# sdc_Sch.net
KiCad netlist of a schematic drawn in Altium Designer
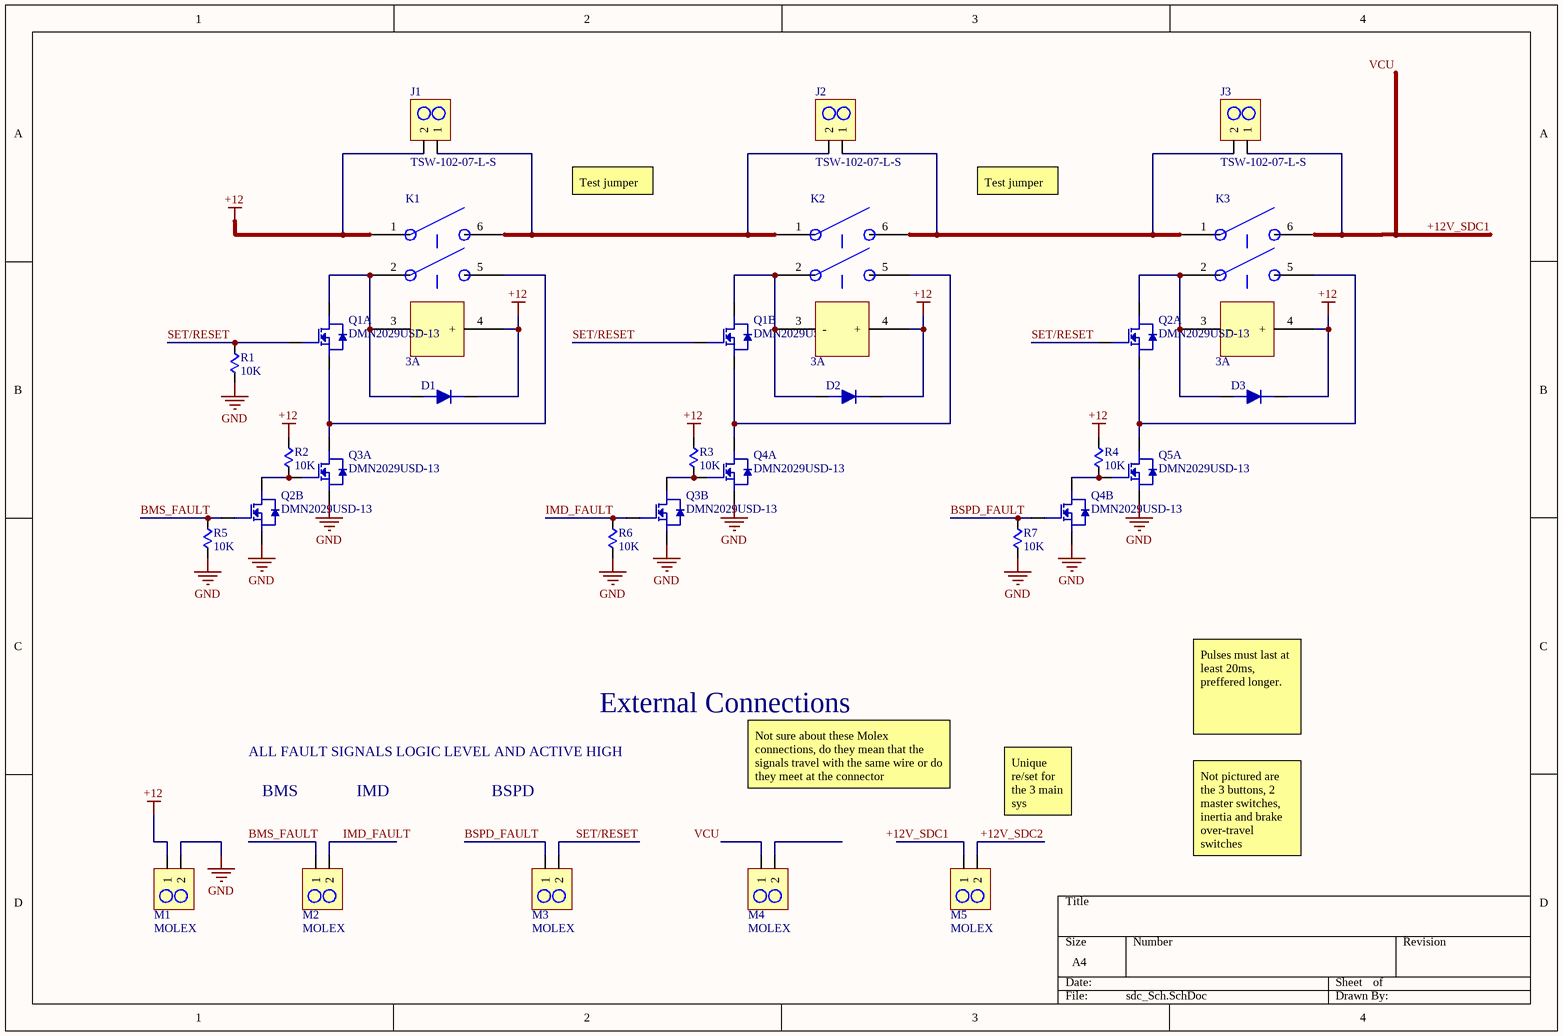
[diagram p0: sdc_Sch.SchDoc]

(export (version "E")
  (design (tool "Eeschema 10.0.6"))
  (components
    (comp (ref "D1")
      (value "SD560BTR")
      (footprint "DIOM4436X26N")
      (description "DIODE GEN PURP 600V 5A SMB")
      (fields (field (name "MANUFACTURER") "SMC"))
      (libsource (lib "latch_sdc_schlib") (part "SD560BTR"))
    )
    (comp (ref "D2")
      (value "SD560BTR")
      (footprint "DIOM4436X26N")
      (description "DIODE GEN PURP 600V 5A SMB")
      (fields (field (name "MANUFACTURER") "SMC"))
      (libsource (lib "latch_sdc_schlib") (part "SD560BTR"))
    )
    (comp (ref "D3")
      (value "SD560BTR")
      (footprint "DIOM4436X26N")
      (description "DIODE GEN PURP 600V 5A SMB")
      (fields (field (name "MANUFACTURER") "SMC"))
      (libsource (lib "latch_sdc_schlib") (part "SD560BTR"))
    )
    (comp (ref "J1")
      (value "TSW-102-07-L-S")
      (footprint "TSW-102-XX-X-S")
      (description "CONN HEADER VERT 2POS 2.54MM")
      (fields (field (name "MANUFACTURER") "Samtec"))
      (libsource (lib "latch_sdc_schlib") (part "TSW-102-07-L-S"))
    )
    (comp (ref "J2")
      (value "TSW-102-07-L-S")
      (footprint "TSW-102-XX-X-S")
      (description "CONN HEADER VERT 2POS 2.54MM")
      (fields (field (name "MANUFACTURER") "Samtec"))
      (libsource (lib "latch_sdc_schlib") (part "TSW-102-07-L-S"))
    )
    (comp (ref "J3")
      (value "TSW-102-07-L-S")
      (footprint "TSW-102-XX-X-S")
      (description "CONN HEADER VERT 2POS 2.54MM")
      (fields (field (name "MANUFACTURER") "Samtec"))
      (libsource (lib "latch_sdc_schlib") (part "TSW-102-07-L-S"))
    )
    (comp (ref "K1")
      (value "3A")
      (footprint "RELAY02_FOOTPRINT")
      (fields
        (field (name "MANUFACTURER") "TE Connectivity")
        (field (name "MANUFACTURER PART NUMBER") "OSA-SS-212DM3,000")
      )
      (libsource (lib "latch_sdc_schlib") (part "OSA-SS-212DM3,000"))
    )
    (comp (ref "K2")
      (value "3A")
      (footprint "RELAY02_FOOTPRINT")
      (fields
        (field (name "MANUFACTURER") "TE Connectivity")
        (field (name "MANUFACTURER PART NUMBER") "OSA-SS-212DM3,000")
      )
      (libsource (lib "latch_sdc_schlib") (part "OSA-SS-212DM3,000"))
    )
    (comp (ref "K3")
      (value "3A")
      (footprint "RELAY02_FOOTPRINT")
      (fields
        (field (name "MANUFACTURER") "TE Connectivity")
        (field (name "MANUFACTURER PART NUMBER") "OSA-SS-212DM3,000")
      )
      (libsource (lib "latch_sdc_schlib") (part "OSA-SS-212DM3,000"))
    )
    (comp (ref "M1")
      (value "MOLEX")
      (footprint "MOLEX 1")
      (description "MOLEX - 43650-0200 - CONNECTOR, HEADER, 2POS, 1ROW, 3MM")
      (fields (field (name "MANUFACTURER") "Molex") (field (name "MANUFACTURER PART NUMBER") "43650-0200"))
      (libsource (lib "latch_sdc_schlib") (part "43650-0200"))
    )
    (comp (ref "M2")
      (value "MOLEX")
      (footprint "MOLEX 1")
      (description "MOLEX - 43650-0200 - CONNECTOR, HEADER, 2POS, 1ROW, 3MM")
      (fields (field (name "MANUFACTURER") "Molex") (field (name "MANUFACTURER PART NUMBER") "43650-0200"))
      (libsource (lib "latch_sdc_schlib") (part "43650-0200"))
    )
    (comp (ref "M3")
      (value "MOLEX")
      (footprint "MOLEX 1")
      (description "MOLEX - 43650-0200 - CONNECTOR, HEADER, 2POS, 1ROW, 3MM")
      (fields (field (name "MANUFACTURER") "Molex") (field (name "MANUFACTURER PART NUMBER") "43650-0200"))
      (libsource (lib "latch_sdc_schlib") (part "43650-0200"))
    )
    (comp (ref "M4")
      (value "MOLEX")
      (footprint "MOLEX 1")
      (description "MOLEX - 43650-0200 - CONNECTOR, HEADER, 2POS, 1ROW, 3MM")
      (fields (field (name "MANUFACTURER") "Molex") (field (name "MANUFACTURER PART NUMBER") "43650-0200"))
      (libsource (lib "latch_sdc_schlib") (part "43650-0200"))
    )
    (comp (ref "M5")
      (value "MOLEX")
      (footprint "MOLEX 1")
      (description "MOLEX - 43650-0200 - CONNECTOR, HEADER, 2POS, 1ROW, 3MM")
      (fields (field (name "MANUFACTURER") "Molex") (field (name "MANUFACTURER PART NUMBER") "43650-0200"))
      (libsource (lib "latch_sdc_schlib") (part "43650-0200"))
    )
    (comp (ref "Q1")
      (value "DMN2029USD-13")
      (footprint "SOIC127P600X175-8N")
      (description "MOSFET 2N-CH 20V 5.8A 8SO")
      (fields (field (name "MANUFACTURER") "Diodes"))
      (libsource (lib "latch_sdc_schlib") (part "DMN2029USD-13"))
    )
    (comp (ref "Q2")
      (value "DMN2029USD-13")
      (footprint "SOIC127P600X175-8N")
      (description "MOSFET 2N-CH 20V 5.8A 8SO")
      (fields (field (name "MANUFACTURER") "Diodes"))
      (libsource (lib "latch_sdc_schlib") (part "DMN2029USD-13"))
    )
    (comp (ref "Q3")
      (value "DMN2029USD-13")
      (footprint "SOIC127P600X175-8N")
      (description "MOSFET 2N-CH 20V 5.8A 8SO")
      (fields (field (name "MANUFACTURER") "Diodes"))
      (libsource (lib "latch_sdc_schlib") (part "DMN2029USD-13"))
    )
    (comp (ref "Q4")
      (value "DMN2029USD-13")
      (footprint "SOIC127P600X175-8N")
      (description "MOSFET 2N-CH 20V 5.8A 8SO")
      (fields (field (name "MANUFACTURER") "Diodes"))
      (libsource (lib "latch_sdc_schlib") (part "DMN2029USD-13"))
    )
    (comp (ref "Q5")
      (value "DMN2029USD-13")
      (footprint "SOIC127P600X175-8N")
      (description "MOSFET 2N-CH 20V 5.8A 8SO")
      (fields (field (name "MANUFACTURER") "Diodes"))
      (libsource (lib "latch_sdc_schlib") (part "DMN2029USD-13"))
    )
    (comp (ref "R1")
      (value "10K")
      (footprint "10KOHM")
      (description "RES 10K OHM 1% 1/8W 0603")
      (fields
        (field (name "MANUFACTURER") "Stackpole Electronics")
        (field (name "MANUFACTURER PART NUMBER") "RNCP0603FTD10K0")
      )
      (libsource (lib "latch_sdc_schlib") (part "RNCP0603FTD10K0"))
    )
    (comp (ref "R2")
      (value "10K")
      (footprint "10KOHM")
      (description "RES 10K OHM 1% 1/8W 0603")
      (fields
        (field (name "MANUFACTURER") "Stackpole Electronics")
        (field (name "MANUFACTURER PART NUMBER") "RNCP0603FTD10K0")
      )
      (libsource (lib "latch_sdc_schlib") (part "RNCP0603FTD10K0"))
    )
    (comp (ref "R3")
      (value "10K")
      (footprint "10KOHM")
      (description "RES 10K OHM 1% 1/8W 0603")
      (fields
        (field (name "MANUFACTURER") "Stackpole Electronics")
        (field (name "MANUFACTURER PART NUMBER") "RNCP0603FTD10K0")
      )
      (libsource (lib "latch_sdc_schlib") (part "RNCP0603FTD10K0"))
    )
    (comp (ref "R4")
      (value "10K")
      (footprint "10KOHM")
      (description "RES 10K OHM 1% 1/8W 0603")
      (fields
        (field (name "MANUFACTURER") "Stackpole Electronics")
        (field (name "MANUFACTURER PART NUMBER") "RNCP0603FTD10K0")
      )
      (libsource (lib "latch_sdc_schlib") (part "RNCP0603FTD10K0"))
    )
    (comp (ref "R5")
      (value "10K")
      (footprint "10KOHM")
      (description "RES 10K OHM 1% 1/8W 0603")
      (fields
        (field (name "MANUFACTURER") "Stackpole Electronics")
        (field (name "MANUFACTURER PART NUMBER") "RNCP0603FTD10K0")
      )
      (libsource (lib "latch_sdc_schlib") (part "RNCP0603FTD10K0"))
    )
    (comp (ref "R6")
      (value "10K")
      (footprint "10KOHM")
      (description "RES 10K OHM 1% 1/8W 0603")
      (fields
        (field (name "MANUFACTURER") "Stackpole Electronics")
        (field (name "MANUFACTURER PART NUMBER") "RNCP0603FTD10K0")
      )
      (libsource (lib "latch_sdc_schlib") (part "RNCP0603FTD10K0"))
    )
    (comp (ref "R7")
      (value "10K")
      (footprint "10KOHM")
      (description "RES 10K OHM 1% 1/8W 0603")
      (fields
        (field (name "MANUFACTURER") "Stackpole Electronics")
        (field (name "MANUFACTURER PART NUMBER") "RNCP0603FTD10K0")
      )
      (libsource (lib "latch_sdc_schlib") (part "RNCP0603FTD10K0"))
    )
  )
  (nets
    (net (code "1") (name "+12") (class "Default")
      (node (ref "D1") (pin "2") (pinfunction "2_2") (pintype "passive"))
      (node (ref "D2") (pin "2") (pinfunction "2_2") (pintype "passive"))
      (node (ref "D3") (pin "2") (pinfunction "2_2") (pintype "passive"))
      (node (ref "J1") (pin "2") (pinfunction "2_2") (pintype "passive"))
      (node (ref "K1") (pin "1") (pintype "passive"))
      (node (ref "K1") (pin "4") (pinfunction "+_4") (pintype "passive"))
      (node (ref "K2") (pin "4") (pinfunction "+_4") (pintype "passive"))
      (node (ref "K3") (pin "4") (pinfunction "+_4") (pintype "passive"))
      (node (ref "M1") (pin "1") (pinfunction "1_1") (pintype "passive"))
      (node (ref "R2") (pin "1") (pinfunction "1_1") (pintype "passive"))
      (node (ref "R3") (pin "1") (pinfunction "1_1") (pintype "passive"))
      (node (ref "R4") (pin "1") (pinfunction "1_1") (pintype "passive"))
    )
    (net (code "2") (name "/+12V_SDC1") (class "Default")
      (node (ref "J3") (pin "1") (pinfunction "1_1") (pintype "passive"))
      (node (ref "K3") (pin "6") (pintype "passive"))
      (node (ref "M4") (pin "1") (pinfunction "1_1") (pintype "passive"))
      (node (ref "M5") (pin "1") (pinfunction "1_1") (pintype "passive"))
    )
    (net (code "3") (name "/+12V_SDC2") (class "Default")
      (node (ref "M5") (pin "2") (pinfunction "2_2") (pintype "passive"))
    )
    (net (code "4") (name "/BMS_FAULT") (class "Default")
      (node (ref "M2") (pin "1") (pinfunction "1_1") (pintype "passive"))
      (node (ref "Q2") (pin "4") (pinfunction "G2_4") (pintype "passive"))
      (node (ref "R5") (pin "1") (pinfunction "1_1") (pintype "passive"))
    )
    (net (code "5") (name "/BSPD_FAULT") (class "Default")
      (node (ref "M3") (pin "1") (pinfunction "1_1") (pintype "passive"))
      (node (ref "Q4") (pin "4") (pinfunction "G2_4") (pintype "passive"))
      (node (ref "R7") (pin "1") (pinfunction "1_1") (pintype "passive"))
    )
    (net (code "6") (name "/IMD_FAULT") (class "Default")
      (node (ref "M2") (pin "2") (pinfunction "2_2") (pintype "passive"))
      (node (ref "Q3") (pin "4") (pinfunction "G2_4") (pintype "passive"))
      (node (ref "R6") (pin "1") (pinfunction "1_1") (pintype "passive"))
    )
    (net (code "7") (name "/SET{slash}RESET") (class "Default")
      (node (ref "M3") (pin "2") (pinfunction "2_2") (pintype "passive"))
      (node (ref "Q1") (pin "2") (pinfunction "G1_2") (pintype "passive"))
      (node (ref "Q1") (pin "4") (pinfunction "G2_4") (pintype "passive"))
      (node (ref "Q2") (pin "2") (pinfunction "G1_2") (pintype "passive"))
      (node (ref "R1") (pin "1") (pinfunction "1_1") (pintype "passive"))
    )
    (net (code "8") (name "GND") (class "Default")
      (node (ref "M1") (pin "2") (pinfunction "2_2") (pintype "passive"))
      (node (ref "Q2") (pin "3") (pinfunction "S2_3") (pintype "passive"))
      (node (ref "Q3") (pin "1") (pinfunction "S1_1") (pintype "passive"))
      (node (ref "Q3") (pin "3") (pinfunction "S2_3") (pintype "passive"))
      (node (ref "Q4") (pin "1") (pinfunction "S1_1") (pintype "passive"))
      (node (ref "Q4") (pin "3") (pinfunction "S2_3") (pintype "passive"))
      (node (ref "Q5") (pin "1") (pinfunction "S1_1") (pintype "passive"))
      (node (ref "R1") (pin "2") (pinfunction "2_2") (pintype "passive"))
      (node (ref "R5") (pin "2") (pinfunction "2_2") (pintype "passive"))
      (node (ref "R6") (pin "2") (pinfunction "2_2") (pintype "passive"))
      (node (ref "R7") (pin "2") (pinfunction "2_2") (pintype "passive"))
    )
    (net (code "9") (name "Net-(J1-Pad1)") (class "Default")
      (node (ref "J1") (pin "1") (pinfunction "1_1") (pintype "passive"))
      (node (ref "J2") (pin "2") (pinfunction "2_2") (pintype "passive"))
      (node (ref "K1") (pin "6") (pintype "passive"))
      (node (ref "K2") (pin "1") (pintype "passive"))
    )
    (net (code "10") (name "Net-(J2-Pad1)") (class "Default")
      (node (ref "J2") (pin "1") (pinfunction "1_1") (pintype "passive"))
      (node (ref "J3") (pin "2") (pinfunction "2_2") (pintype "passive"))
      (node (ref "K2") (pin "6") (pintype "passive"))
      (node (ref "K3") (pin "1") (pintype "passive"))
    )
    (net (code "11") (name "Net-(K1--)") (class "Default")
      (node (ref "D1") (pin "1") (pinfunction "1_1") (pintype "passive"))
      (node (ref "K1") (pin "2") (pintype "passive"))
      (node (ref "K1") (pin "3") (pinfunction "-_3") (pintype "passive"))
      (node (ref "Q1") (pin "8") (pinfunction "D1_8") (pintype "passive"))
    )
    (net (code "12") (name "Net-(K2--)") (class "Default")
      (node (ref "D2") (pin "1") (pinfunction "1_1") (pintype "passive"))
      (node (ref "K2") (pin "2") (pintype "passive"))
      (node (ref "K2") (pin "3") (pinfunction "-_3") (pintype "passive"))
      (node (ref "Q1") (pin "5") (pinfunction "D2_5") (pintype "passive"))
    )
    (net (code "13") (name "Net-(K3--)") (class "Default")
      (node (ref "D3") (pin "1") (pinfunction "1_1") (pintype "passive"))
      (node (ref "K3") (pin "2") (pintype "passive"))
      (node (ref "K3") (pin "3") (pinfunction "-_3") (pintype "passive"))
      (node (ref "Q2") (pin "8") (pinfunction "D1_8") (pintype "passive"))
    )
    (net (code "14") (name "Net-(Q1A-S1)") (class "Default")
      (node (ref "K1") (pin "5") (pintype "passive"))
      (node (ref "Q1") (pin "1") (pinfunction "S1_1") (pintype "passive"))
      (node (ref "Q3") (pin "8") (pinfunction "D1_8") (pintype "passive"))
    )
    (net (code "15") (name "Net-(Q1B-S2)") (class "Default")
      (node (ref "K2") (pin "5") (pintype "passive"))
      (node (ref "Q1") (pin "3") (pinfunction "S2_3") (pintype "passive"))
      (node (ref "Q4") (pin "8") (pinfunction "D1_8") (pintype "passive"))
    )
    (net (code "16") (name "Net-(Q2A-S1)") (class "Default")
      (node (ref "K3") (pin "5") (pintype "passive"))
      (node (ref "Q2") (pin "1") (pinfunction "S1_1") (pintype "passive"))
      (node (ref "Q5") (pin "8") (pinfunction "D1_8") (pintype "passive"))
    )
    (net (code "17") (name "Net-(Q2B-D2)") (class "Default")
      (node (ref "Q2") (pin "5") (pinfunction "D2_5") (pintype "passive"))
      (node (ref "Q3") (pin "2") (pinfunction "G1_2") (pintype "passive"))
      (node (ref "R2") (pin "2") (pinfunction "2_2") (pintype "passive"))
    )
    (net (code "18") (name "Net-(Q3B-D2)") (class "Default")
      (node (ref "Q3") (pin "5") (pinfunction "D2_5") (pintype "passive"))
      (node (ref "Q4") (pin "2") (pinfunction "G1_2") (pintype "passive"))
      (node (ref "R3") (pin "2") (pinfunction "2_2") (pintype "passive"))
    )
    (net (code "19") (name "Net-(Q4B-D2)") (class "Default")
      (node (ref "Q4") (pin "5") (pinfunction "D2_5") (pintype "passive"))
      (node (ref "Q5") (pin "2") (pinfunction "G1_2") (pintype "passive"))
      (node (ref "R4") (pin "2") (pinfunction "2_2") (pintype "passive"))
    )
    (net (code "20") (name "unconnected-(M4-Pad2)") (class "Default")
      (node (ref "M4") (pin "2") (pinfunction "2_2") (pintype "passive"))
    )
  )
)
